# 3_Connectors.net
KiCad netlist of a schematic drawn in Altium Designer
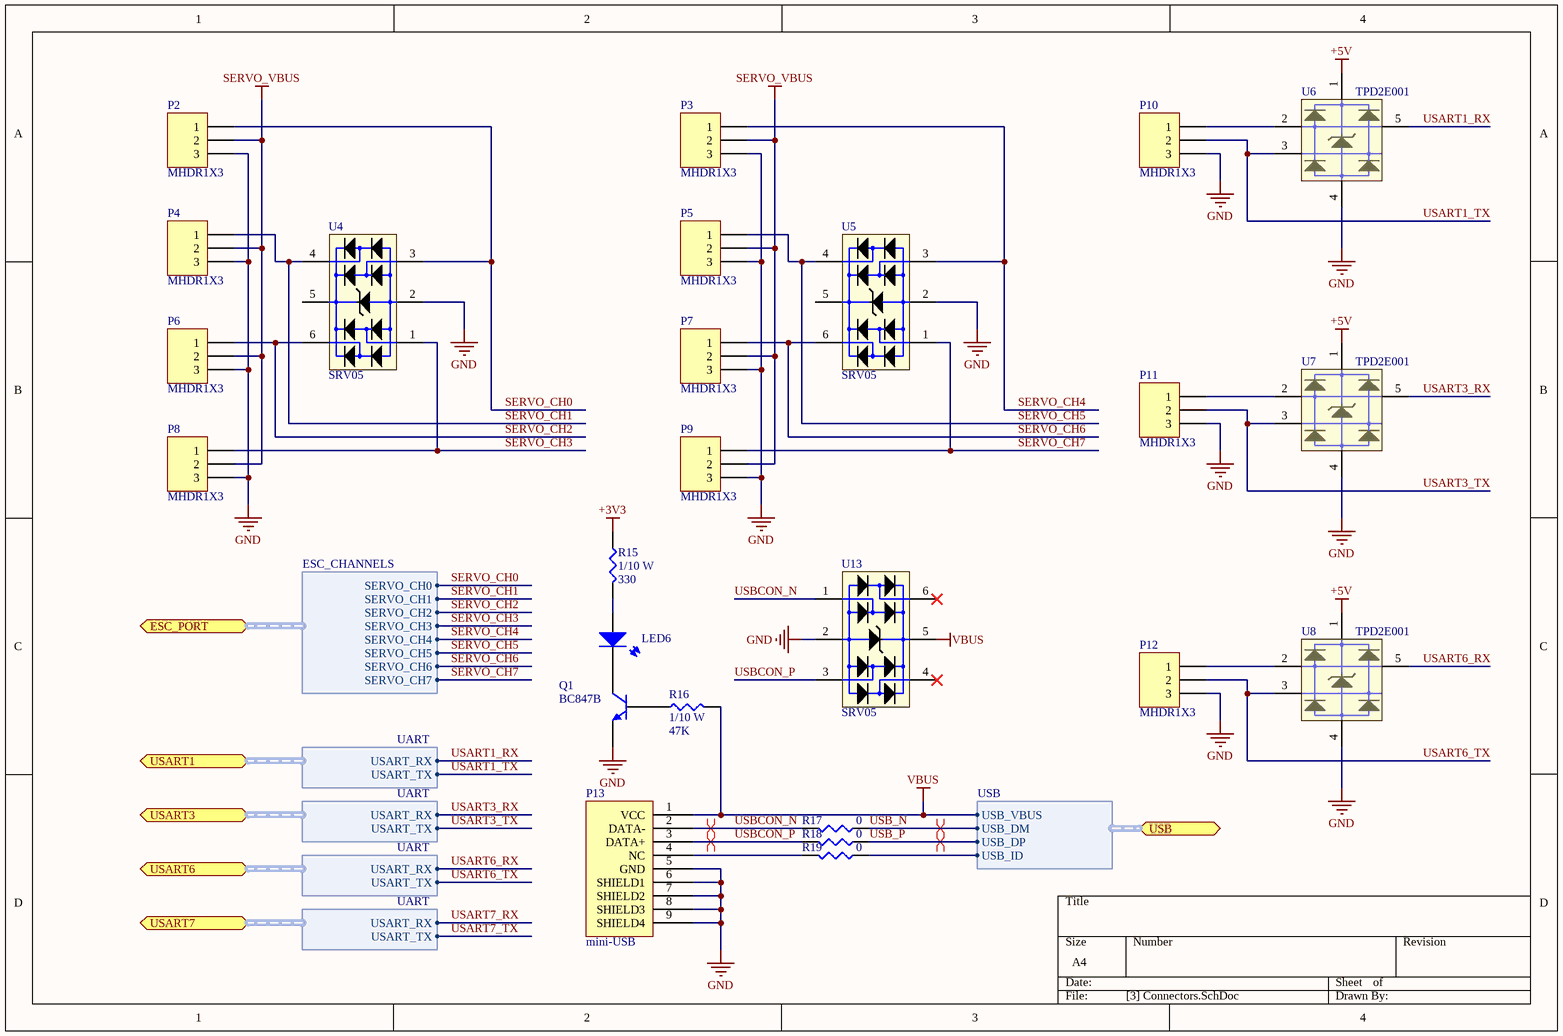
[diagram p0: [3] Connectors.SchDoc]

(export (version "E")
  (design (tool "Eeschema 10.0.6"))
  (components
    (comp (ref "LED6") (value "LED 0603") (footprint "LED 0603") (libsource (lib "LEDs") (part "LED0603")))
    (comp (ref "P2")
      (value "MHDR1X3")
      (footprint "MHDR1X3")
      (description "Header, 3-Pin")
      (fields (field (name "PUBLISHER") "Altium Limited"))
      (libsource (lib "Miscellaneous Connectors") (part "MHDR1X3"))
    )
    (comp (ref "P3")
      (value "MHDR1X3")
      (footprint "MHDR1X3")
      (description "Header, 3-Pin")
      (fields (field (name "PUBLISHER") "Altium Limited"))
      (libsource (lib "Miscellaneous Connectors") (part "MHDR1X3"))
    )
    (comp (ref "P4")
      (value "MHDR1X3")
      (footprint "MHDR1X3")
      (description "Header, 3-Pin")
      (fields (field (name "PUBLISHER") "Altium Limited"))
      (libsource (lib "Miscellaneous Connectors") (part "MHDR1X3"))
    )
    (comp (ref "P5")
      (value "MHDR1X3")
      (footprint "MHDR1X3")
      (description "Header, 3-Pin")
      (fields (field (name "PUBLISHER") "Altium Limited"))
      (libsource (lib "Miscellaneous Connectors") (part "MHDR1X3"))
    )
    (comp (ref "P6")
      (value "MHDR1X3")
      (footprint "MHDR1X3")
      (description "Header, 3-Pin")
      (fields (field (name "PUBLISHER") "Altium Limited"))
      (libsource (lib "Miscellaneous Connectors") (part "MHDR1X3"))
    )
    (comp (ref "P7")
      (value "MHDR1X3")
      (footprint "MHDR1X3")
      (description "Header, 3-Pin")
      (fields (field (name "PUBLISHER") "Altium Limited"))
      (libsource (lib "Miscellaneous Connectors") (part "MHDR1X3"))
    )
    (comp (ref "P8")
      (value "MHDR1X3")
      (footprint "MHDR1X3")
      (description "Header, 3-Pin")
      (fields (field (name "PUBLISHER") "Altium Limited"))
      (libsource (lib "Miscellaneous Connectors") (part "MHDR1X3"))
    )
    (comp (ref "P9")
      (value "MHDR1X3")
      (footprint "MHDR1X3")
      (description "Header, 3-Pin")
      (fields (field (name "PUBLISHER") "Altium Limited"))
      (libsource (lib "Miscellaneous Connectors") (part "MHDR1X3"))
    )
    (comp (ref "P10")
      (value "MHDR1X3")
      (footprint "MHDR1X3")
      (description "Header, 3-Pin")
      (fields (field (name "PUBLISHER") "Altium Limited"))
      (libsource (lib "Miscellaneous Connectors") (part "MHDR1X3"))
    )
    (comp (ref "P11")
      (value "MHDR1X3")
      (footprint "MHDR1X3")
      (description "Header, 3-Pin")
      (fields (field (name "PUBLISHER") "Altium Limited"))
      (libsource (lib "Miscellaneous Connectors") (part "MHDR1X3"))
    )
    (comp (ref "P12")
      (value "MHDR1X3")
      (footprint "MHDR1X3")
      (description "Header, 3-Pin")
      (fields (field (name "PUBLISHER") "Altium Limited"))
      (libsource (lib "Miscellaneous Connectors") (part "MHDR1X3"))
    )
    (comp (ref "P13")
      (value "mini-USB")
      (footprint "USB/SM0.8-6H5")
      (libsource (lib "Connectors") (part "miniUSB"))
    )
    (comp (ref "Q1")
      (value "BC847B")
      (footprint "SOT23")
      (description "SOT23 NPN Silicon Planar General Purpose Transistor")
      (fields (field (name "PUBLISHER") "Altium Limited"))
      (libsource (lib "Zetex Discrete BJT") (part "BC847B"))
    )
    (comp (ref "R15")
      (value "330")
      (footprint "RES0805")
      (description "Think Film Chip resistor")
      (fields
        (field (name "TOLERANCE") "1%")
        (field (name "RATING") "1/10 W")
        (field (name "Comment") "ChipRes 330R 1%")
      )
      (libsource (lib "Resistors") (part "ChipRes 330R 1%"))
    )
    (comp (ref "R16")
      (value "47K")
      (footprint "RES0805")
      (description "Think Film Chip resistor")
      (fields
        (field (name "TOLERANCE") "1%")
        (field (name "RATING") "1/10 W")
        (field (name "Comment") "ChipRes 47K 1%")
      )
      (libsource (lib "Resistors") (part "ChipRes 47K 1%"))
    )
    (comp (ref "R17")
      (value "0")
      (footprint "RES0805")
      (description "Chip resistor")
      (fields (field (name "Comment") "ChipRes"))
      (libsource (lib "Common Devices") (part "ChipRes"))
    )
    (comp (ref "R18")
      (value "0")
      (footprint "RES0805")
      (description "Chip resistor")
      (fields (field (name "Comment") "ChipRes"))
      (libsource (lib "Common Devices") (part "ChipRes"))
    )
    (comp (ref "R19")
      (value "0")
      (footprint "RES0805")
      (description "Chip resistor")
      (fields (field (name "Comment") "ChipRes"))
      (libsource (lib "Common Devices") (part "ChipRes"))
    )
    (comp (ref "U4")
      (value "SRV05")
      (footprint "SOT23-6")
      (description "Protection 6V 10A")
      (libsource (lib "Protection") (part "SRV05"))
    )
    (comp (ref "U5")
      (value "SRV05")
      (footprint "SOT23-6")
      (description "Protection 6V 10A")
      (libsource (lib "Protection") (part "SRV05"))
    )
    (comp (ref "U6")
      (value "TPD2E001")
      (footprint "SOT23-5")
      (description "Low-Capacitance 2-Channel ESD-Protection for High-Speed Data Interfaces")
      (libsource (lib "Protection") (part "TPD2E001"))
    )
    (comp (ref "U7")
      (value "TPD2E001")
      (footprint "SOT23-5")
      (description "Low-Capacitance 2-Channel ESD-Protection for High-Speed Data Interfaces")
      (libsource (lib "Protection") (part "TPD2E001"))
    )
    (comp (ref "U8")
      (value "TPD2E001")
      (footprint "SOT23-5")
      (description "Low-Capacitance 2-Channel ESD-Protection for High-Speed Data Interfaces")
      (libsource (lib "Protection") (part "TPD2E001"))
    )
    (comp (ref "U13")
      (value "SRV05")
      (footprint "SOT23-6")
      (description "Protection 6V 10A")
      (libsource (lib "Protection") (part "SRV05"))
    )
  )
  (nets
    (net (code "4") (name "+3V3") (class "Default") (node (ref "R15") (pin "1") (pintype "passive")))
    (net (code "5") (name "+5V") (class "Default")
      (node (ref "U6") (pin "1") (pinfunction "1_1") (pintype "passive"))
      (node (ref "U7") (pin "1") (pinfunction "1_1") (pintype "passive"))
      (node (ref "U8") (pin "1") (pinfunction "1_1") (pintype "passive"))
    )
    (net (code "6") (name "/SERVO_CH0") (class "Default")
      (node (ref "P2") (pin "1") (pinfunction "1_1") (pintype "passive"))
      (node (ref "U4") (pin "3") (pinfunction "3_3") (pintype "passive"))
    )
    (net (code "7") (name "/SERVO_CH1") (class "Default")
      (node (ref "P4") (pin "1") (pinfunction "1_1") (pintype "passive"))
      (node (ref "U4") (pin "4") (pinfunction "4_4") (pintype "passive"))
    )
    (net (code "8") (name "/SERVO_CH2") (class "Default")
      (node (ref "P6") (pin "1") (pinfunction "1_1") (pintype "passive"))
      (node (ref "U4") (pin "6") (pinfunction "6_6") (pintype "passive"))
    )
    (net (code "9") (name "/SERVO_CH3") (class "Default")
      (node (ref "P8") (pin "1") (pinfunction "1_1") (pintype "passive"))
      (node (ref "U4") (pin "1") (pinfunction "1_1") (pintype "passive"))
    )
    (net (code "10") (name "/SERVO_CH4") (class "Default")
      (node (ref "P3") (pin "1") (pinfunction "1_1") (pintype "passive"))
      (node (ref "U5") (pin "3") (pinfunction "3_3") (pintype "passive"))
    )
    (net (code "11") (name "/SERVO_CH5") (class "Default")
      (node (ref "P5") (pin "1") (pinfunction "1_1") (pintype "passive"))
      (node (ref "U5") (pin "4") (pinfunction "4_4") (pintype "passive"))
    )
    (net (code "12") (name "/SERVO_CH6") (class "Default")
      (node (ref "P7") (pin "1") (pinfunction "1_1") (pintype "passive"))
      (node (ref "U5") (pin "6") (pinfunction "6_6") (pintype "passive"))
    )
    (net (code "13") (name "/SERVO_CH7") (class "Default")
      (node (ref "P9") (pin "1") (pinfunction "1_1") (pintype "passive"))
      (node (ref "U5") (pin "1") (pinfunction "1_1") (pintype "passive"))
    )
    (net (code "14") (name "/USART1_RX") (class "Default")
      (node (ref "U6") (pin "5") (pinfunction "5_5") (pintype "passive"))
    )
    (net (code "15") (name "/USART1_TX") (class "Default")
      (node (ref "P10") (pin "2") (pinfunction "2_2") (pintype "passive"))
      (node (ref "U6") (pin "3") (pinfunction "3_3") (pintype "passive"))
    )
    (net (code "16") (name "/USART3_RX") (class "Default")
      (node (ref "U7") (pin "5") (pinfunction "5_5") (pintype "passive"))
    )
    (net (code "17") (name "/USART3_TX") (class "Default")
      (node (ref "P11") (pin "2") (pinfunction "2_2") (pintype "passive"))
      (node (ref "U7") (pin "3") (pinfunction "3_3") (pintype "passive"))
    )
    (net (code "18") (name "/USART6_RX") (class "Default")
      (node (ref "U8") (pin "5") (pinfunction "5_5") (pintype "passive"))
    )
    (net (code "19") (name "/USART6_TX") (class "Default")
      (node (ref "P12") (pin "2") (pinfunction "2_2") (pintype "passive"))
      (node (ref "U8") (pin "3") (pinfunction "3_3") (pintype "passive"))
    )
    (net (code "22") (name "/USBCON_N") (class "Default")
      (node (ref "P13") (pin "2") (pinfunction "DATA-_2") (pintype "passive"))
      (node (ref "R17") (pin "2") (pintype "passive"))
      (node (ref "U13") (pin "1") (pinfunction "1_1") (pintype "passive"))
    )
    (net (code "23") (name "/USBCON_P") (class "Default")
      (node (ref "P13") (pin "3") (pinfunction "DATA+_3") (pintype "passive"))
      (node (ref "R18") (pin "2") (pintype "passive"))
      (node (ref "U13") (pin "3") (pinfunction "3_3") (pintype "passive"))
    )
    (net (code "24") (name "/USB_ID") (class "Default") (node (ref "R19") (pin "1") (pintype "passive")))
    (net (code "25") (name "/USB_N") (class "Default") (node (ref "R17") (pin "1") (pintype "passive")))
    (net (code "26") (name "/USB_P") (class "Default") (node (ref "R18") (pin "1") (pintype "passive")))
    (net (code "30") (name "GND") (class "Default")
      (node (ref "P10") (pin "3") (pinfunction "3_3") (pintype "passive"))
      (node (ref "P11") (pin "3") (pinfunction "3_3") (pintype "passive"))
      (node (ref "P12") (pin "3") (pinfunction "3_3") (pintype "passive"))
      (node (ref "P13") (pin "5") (pinfunction "GND_5") (pintype "passive"))
      (node (ref "P13") (pin "6") (pinfunction "SHIELD1_6") (pintype "passive"))
      (node (ref "P13") (pin "7") (pinfunction "SHIELD2_7") (pintype "passive"))
      (node (ref "P13") (pin "8") (pinfunction "SHIELD3_8") (pintype "passive"))
      (node (ref "P13") (pin "9") (pinfunction "SHIELD4_9") (pintype "passive"))
      (node (ref "P2") (pin "3") (pinfunction "3_3") (pintype "passive"))
      (node (ref "P3") (pin "3") (pinfunction "3_3") (pintype "passive"))
      (node (ref "P4") (pin "3") (pinfunction "3_3") (pintype "passive"))
      (node (ref "P5") (pin "3") (pinfunction "3_3") (pintype "passive"))
      (node (ref "P6") (pin "3") (pinfunction "3_3") (pintype "passive"))
      (node (ref "P7") (pin "3") (pinfunction "3_3") (pintype "passive"))
      (node (ref "P8") (pin "3") (pinfunction "3_3") (pintype "passive"))
      (node (ref "P9") (pin "3") (pinfunction "3_3") (pintype "passive"))
      (node (ref "Q1") (pin "2") (pinfunction "E_2") (pintype "passive"))
      (node (ref "U13") (pin "2") (pinfunction "2_2") (pintype "passive"))
      (node (ref "U4") (pin "2") (pinfunction "2_2") (pintype "passive"))
      (node (ref "U5") (pin "2") (pinfunction "2_2") (pintype "passive"))
      (node (ref "U6") (pin "4") (pinfunction "4_4") (pintype "passive"))
      (node (ref "U7") (pin "4") (pinfunction "4_4") (pintype "passive"))
      (node (ref "U8") (pin "4") (pinfunction "4_4") (pintype "passive"))
    )
    (net (code "31") (name "Net-(LED6-Pad2)") (class "Default")
      (node (ref "LED6") (pin "2") (pinfunction "2_2") (pintype "passive"))
      (node (ref "R15") (pin "2") (pintype "passive"))
    )
    (net (code "32") (name "Net-(P10-Pad1)") (class "Default")
      (node (ref "P10") (pin "1") (pinfunction "1_1") (pintype "passive"))
      (node (ref "U6") (pin "2") (pinfunction "2_2") (pintype "passive"))
    )
    (net (code "33") (name "Net-(P11-Pad1)") (class "Default")
      (node (ref "P11") (pin "1") (pinfunction "1_1") (pintype "passive"))
      (node (ref "U7") (pin "2") (pinfunction "2_2") (pintype "passive"))
    )
    (net (code "34") (name "Net-(P12-Pad1)") (class "Default")
      (node (ref "P12") (pin "1") (pinfunction "1_1") (pintype "passive"))
      (node (ref "U8") (pin "2") (pinfunction "2_2") (pintype "passive"))
    )
    (net (code "35") (name "Net-(P13-NC)") (class "Default")
      (node (ref "P13") (pin "4") (pinfunction "NC_4") (pintype "passive"))
      (node (ref "R19") (pin "2") (pintype "passive"))
    )
    (net (code "36") (name "Net-(Q1-B)") (class "Default")
      (node (ref "Q1") (pin "3") (pinfunction "B_3") (pintype "passive"))
      (node (ref "R16") (pin "1") (pintype "passive"))
    )
    (net (code "37") (name "Net-(Q1-C)") (class "Default")
      (node (ref "LED6") (pin "1") (pinfunction "1_1") (pintype "passive"))
      (node (ref "Q1") (pin "1") (pinfunction "C_1") (pintype "passive"))
    )
    (net (code "38") (name "SERVO_VBUS") (class "Default")
      (node (ref "P2") (pin "2") (pinfunction "2_2") (pintype "passive"))
      (node (ref "P3") (pin "2") (pinfunction "2_2") (pintype "passive"))
      (node (ref "P4") (pin "2") (pinfunction "2_2") (pintype "passive"))
      (node (ref "P5") (pin "2") (pinfunction "2_2") (pintype "passive"))
      (node (ref "P6") (pin "2") (pinfunction "2_2") (pintype "passive"))
      (node (ref "P7") (pin "2") (pinfunction "2_2") (pintype "passive"))
      (node (ref "P8") (pin "2") (pinfunction "2_2") (pintype "passive"))
      (node (ref "P9") (pin "2") (pinfunction "2_2") (pintype "passive"))
    )
    (net (code "39") (name "VBUS") (class "Default")
      (node (ref "P13") (pin "1") (pinfunction "VCC_1") (pintype "passive"))
      (node (ref "R16") (pin "2") (pintype "passive"))
      (node (ref "U13") (pin "5") (pinfunction "5_5") (pintype "passive"))
    )
    (net (code "40") (name "unconnected-(U4-Pad5)") (class "Default")
      (node (ref "U4") (pin "5") (pinfunction "5_5") (pintype "passive"))
    )
    (net (code "41") (name "unconnected-(U5-Pad5)") (class "Default")
      (node (ref "U5") (pin "5") (pinfunction "5_5") (pintype "passive"))
    )
    (net (code "42") (name "unconnected-(U13-Pad4)") (class "Default")
      (node (ref "U13") (pin "4") (pinfunction "4_4") (pintype "passive+no_connect"))
    )
    (net (code "43") (name "unconnected-(U13-Pad6)") (class "Default")
      (node (ref "U13") (pin "6") (pinfunction "6_6") (pintype "passive+no_connect"))
    )
  )
)
